# 30x70-motor-controller-0_4.net
KiCad netlist of a schematic drawn in EAGLE
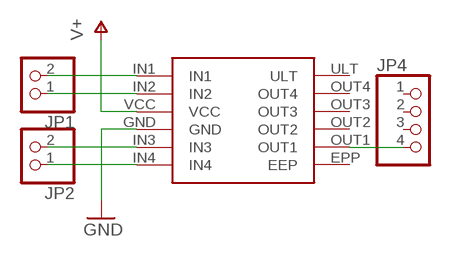
[diagram p0: schematic, sheet 1]
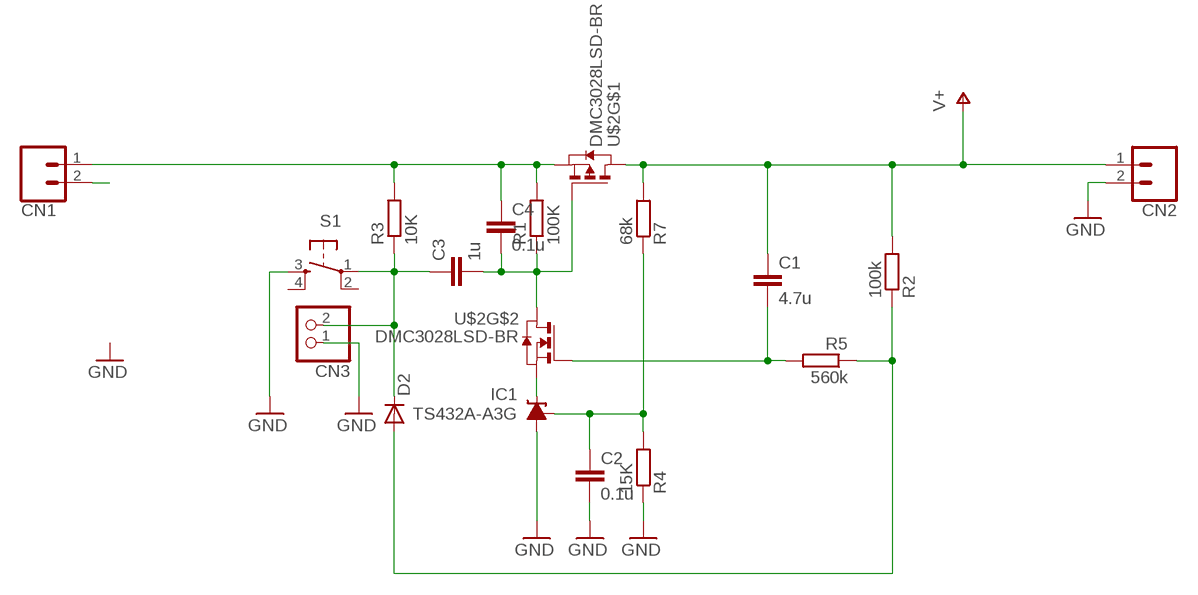
[diagram p1: schematic, sheet 2]

(export (version "E")
  (design (tool "Eeschema 10.0.6"))
  (components
    (comp (ref "C1")
      (value "4.7u")
      (footprint "eagle-import:C025-025X050")
      (libsource (lib "eagle-import") (part "C-EU025-025X050"))
    )
    (comp (ref "C2")
      (value "0.1u")
      (footprint "eagle-import:C025-024X044")
      (libsource (lib "eagle-import") (part "C-EU025-024X044"))
    )
    (comp (ref "C3")
      (value "1u")
      (footprint "eagle-import:C025-024X044")
      (libsource (lib "eagle-import") (part "C-EU025-024X044"))
    )
    (comp (ref "C4")
      (value "0.1u")
      (footprint "eagle-import:C025-024X044")
      (libsource (lib "eagle-import") (part "C-EU025-024X044"))
    )
    (comp (ref "CN1")
      (value "CONN_02-JST-XTH")
      (footprint "eagle-import:JST-2-XTH")
      (libsource (lib "eagle-import") (part "CONN_02-JST-XTH"))
    )
    (comp (ref "CN2")
      (value "CONN_02-JST-XTH")
      (footprint "eagle-import:JST-2-XTH")
      (libsource (lib "eagle-import") (part "CONN_02-JST-XTH"))
    )
    (comp (ref "CN3")
      (value "PINHD-1X2/90")
      (footprint "eagle-import:1X02_90")
      (libsource (lib "eagle-import") (part "PINHD-1X2/90"))
    )
    (comp (ref "D2")
      (value "DIODE-D-2.5")
      (footprint "eagle-import:D-2.5")
      (libsource (lib "eagle-import") (part "DIODE-D-2.5"))
    )
    (comp (ref "IC1")
      (value "TS432A-A3G")
      (footprint "eagle-import:TO92-LINE")
      (libsource (lib "eagle-import") (part "TS432A-A3G"))
    )
    (comp (ref "R1")
      (value "100K")
      (footprint "eagle-import:0204V")
      (libsource (lib "eagle-import") (part "R-EU_0204/2V"))
    )
    (comp (ref "R2")
      (value "100k")
      (footprint "eagle-import:0204V")
      (libsource (lib "eagle-import") (part "R-EU_0204/2V"))
    )
    (comp (ref "R3")
      (value "10K")
      (footprint "eagle-import:0204V")
      (libsource (lib "eagle-import") (part "R-EU_0204/2V"))
    )
    (comp (ref "R4")
      (value "15K")
      (footprint "eagle-import:0204V")
      (libsource (lib "eagle-import") (part "R-EU_0204/2V"))
    )
    (comp (ref "R5")
      (value "560k")
      (footprint "eagle-import:0204_7")
      (libsource (lib "eagle-import") (part "R-EU_0204/7"))
    )
    (comp (ref "R7")
      (value "68k")
      (footprint "eagle-import:0204_7")
      (libsource (lib "eagle-import") (part "R-EU_0204/7"))
    )
    (comp (ref "S1")
      (value "PROTO-MICRO-SWITCH")
      (footprint "eagle-import:B3F-10XX-PROTO")
      (libsource (lib "eagle-import") (part "PROTO-MICRO-SWITCH"))
    )
    (comp (ref "U$2")
      (value "DMC3028LSD-BR")
      (footprint "eagle-import:DIL8-BREAKOUT")
      (libsource (lib "eagle-import") (part "DMC3028LSD-BR"))
    )
    (comp (ref "JP1")
      (value "PINHD-1X2/90")
      (footprint "eagle-import:1X02_90")
      (libsource (lib "eagle-import") (part "PINHD-1X2/90"))
    )
    (comp (ref "JP2")
      (value "PINHD-1X2/90")
      (footprint "eagle-import:1X02_90")
      (libsource (lib "eagle-import") (part "PINHD-1X2/90"))
    )
    (comp (ref "JP4")
      (value "PINHD-1X4/90")
      (footprint "eagle-import:1X04_90")
      (libsource (lib "eagle-import") (part "PINHD-1X4/90"))
    )
    (comp (ref "U$1")
      (value "DRV8833-MODULE")
      (footprint "eagle-import:DRV8833-BRKOUT")
      (libsource (lib "eagle-import") (part "DRV8833-MODULE"))
    )
  )
  (nets
    (net (code "1") (name "GND") (class "Default")
      (node (ref "C2") (pin "2") (pinfunction "2_2") (pintype "passive"))
      (node (ref "CN2") (pin "2") (pinfunction "2_2") (pintype "passive"))
      (node (ref "CN3") (pin "1") (pinfunction "1_1") (pintype "passive"))
      (node (ref "IC1") (pin "2") (pinfunction "A_2") (pintype "passive"))
      (node (ref "R4") (pin "1") (pinfunction "1_1") (pintype "passive"))
      (node (ref "S1") (pin "3") (pinfunction "S_3") (pintype "passive"))
      (node (ref "U$1") (pin "GND") (pinfunction "GND_GND") (pintype "bidirectional"))
    )
    (net (code "2") (name "Net-(D2-PadA)") (class "Default")
      (node (ref "D2") (pin "A") (pinfunction "A_A") (pintype "passive"))
      (node (ref "R2") (pin "1") (pinfunction "1_1") (pintype "passive"))
      (node (ref "R5") (pin "1") (pinfunction "1_1") (pintype "passive"))
    )
    (net (code "3") (name "Net-(IC1-C)") (class "Default")
      (node (ref "IC1") (pin "1") (pinfunction "C_1") (pintype "passive"))
      (node (ref "U$2") (pin "1") (pinfunction "S_1") (pintype "passive"))
    )
    (net (code "4") (name "Net-(IC1-FB)") (class "Default")
      (node (ref "C2") (pin "1") (pinfunction "1_1") (pintype "passive"))
      (node (ref "IC1") (pin "3") (pinfunction "FB_3") (pintype "passive"))
      (node (ref "R4") (pin "2") (pinfunction "2_2") (pintype "passive"))
      (node (ref "R7") (pin "1") (pinfunction "1_1") (pintype "passive"))
    )
    (net (code "5") (name "Net-(JP1-Pad1)") (class "Default")
      (node (ref "JP1") (pin "1") (pinfunction "1_1") (pintype "passive"))
      (node (ref "U$1") (pin "IN2") (pinfunction "IN2_IN2") (pintype "bidirectional"))
    )
    (net (code "6") (name "Net-(JP1-Pad2)") (class "Default")
      (node (ref "JP1") (pin "2") (pinfunction "2_2") (pintype "passive"))
      (node (ref "U$1") (pin "IN1") (pinfunction "IN1_IN1") (pintype "bidirectional"))
    )
    (net (code "7") (name "Net-(JP2-Pad1)") (class "Default")
      (node (ref "JP2") (pin "1") (pinfunction "1_1") (pintype "passive"))
      (node (ref "U$1") (pin "IN4") (pinfunction "IN4_IN4") (pintype "bidirectional"))
    )
    (net (code "8") (name "Net-(JP2-Pad2)") (class "Default")
      (node (ref "JP2") (pin "2") (pinfunction "2_2") (pintype "passive"))
      (node (ref "U$1") (pin "IN3") (pinfunction "IN3_IN3") (pintype "bidirectional"))
    )
    (net (code "9") (name "Net-(JP4-Pad4)") (class "Default")
      (node (ref "JP4") (pin "4") (pinfunction "4_4") (pintype "passive"))
      (node (ref "U$1") (pin "OUT1") (pinfunction "OUT1_OUT1") (pintype "bidirectional"))
    )
    (net (code "10") (name "Net-(S1-P)") (class "Default")
      (node (ref "C3") (pin "1") (pinfunction "1_1") (pintype "passive"))
      (node (ref "CN3") (pin "2") (pinfunction "2_2") (pintype "passive"))
      (node (ref "D2") (pin "C") (pinfunction "C_C") (pintype "passive"))
      (node (ref "R3") (pin "1") (pinfunction "1_1") (pintype "passive"))
      (node (ref "S1") (pin "1") (pinfunction "P_1") (pintype "passive"))
    )
    (net (code "11") (name "Net-(U$2A-G)") (class "Default")
      (node (ref "C3") (pin "2") (pinfunction "2_2") (pintype "passive"))
      (node (ref "C4") (pin "2") (pinfunction "2_2") (pintype "passive"))
      (node (ref "R1") (pin "1") (pinfunction "1_1") (pintype "passive"))
      (node (ref "U$2") (pin "4") (pinfunction "G_4") (pintype "passive"))
      (node (ref "U$2") (pin "7") (pinfunction "D_7") (pintype "passive"))
      (node (ref "U$2") (pin "8") (pinfunction "D_8") (pintype "passive"))
    )
    (net (code "12") (name "Net-(U$2A-S)") (class "Default")
      (node (ref "C4") (pin "1") (pinfunction "1_1") (pintype "passive"))
      (node (ref "CN1") (pin "1") (pinfunction "1_1") (pintype "passive"))
      (node (ref "R1") (pin "2") (pinfunction "2_2") (pintype "passive"))
      (node (ref "R3") (pin "2") (pinfunction "2_2") (pintype "passive"))
      (node (ref "U$2") (pin "3") (pinfunction "S_3") (pintype "passive"))
    )
    (net (code "13") (name "Net-(U$2B-G)") (class "Default")
      (node (ref "C1") (pin "2") (pinfunction "2_2") (pintype "passive"))
      (node (ref "R5") (pin "2") (pinfunction "2_2") (pintype "passive"))
      (node (ref "U$2") (pin "2") (pinfunction "G_2") (pintype "passive"))
    )
    (net (code "14") (name "V+") (class "Default")
      (node (ref "C1") (pin "1") (pinfunction "1_1") (pintype "passive"))
      (node (ref "CN2") (pin "1") (pinfunction "1_1") (pintype "passive"))
      (node (ref "R2") (pin "2") (pinfunction "2_2") (pintype "passive"))
      (node (ref "R7") (pin "2") (pinfunction "2_2") (pintype "passive"))
      (node (ref "U$1") (pin "VCC") (pinfunction "VCC_VCC") (pintype "bidirectional"))
      (node (ref "U$2") (pin "5") (pinfunction "D_5") (pintype "passive"))
      (node (ref "U$2") (pin "6") (pinfunction "D_6") (pintype "passive"))
    )
    (net (code "15") (name "unconnected-(CN1-Pad2)") (class "Default")
      (node (ref "CN1") (pin "2") (pinfunction "2_2") (pintype "passive"))
    )
    (net (code "16") (name "unconnected-(JP4-Pad1)") (class "Default")
      (node (ref "JP4") (pin "1") (pinfunction "1_1") (pintype "passive"))
    )
    (net (code "17") (name "unconnected-(JP4-Pad2)") (class "Default")
      (node (ref "JP4") (pin "2") (pinfunction "2_2") (pintype "passive"))
    )
    (net (code "18") (name "unconnected-(JP4-Pad3)") (class "Default")
      (node (ref "JP4") (pin "3") (pinfunction "3_3") (pintype "passive"))
    )
    (net (code "19") (name "unconnected-(S1-P1-Pad2)") (class "Default")
      (node (ref "S1") (pin "2") (pinfunction "P1_2") (pintype "passive"))
    )
    (net (code "20") (name "unconnected-(S1-S1-Pad4)") (class "Default")
      (node (ref "S1") (pin "4") (pinfunction "S1_4") (pintype "passive"))
    )
    (net (code "21") (name "unconnected-(U$1-EEP-PadEPP)") (class "Default")
      (node (ref "U$1") (pin "EPP") (pinfunction "EEP_EPP") (pintype "bidirectional"))
    )
    (net (code "22") (name "unconnected-(U$1-PadOUT2)") (class "Default")
      (node (ref "U$1") (pin "OUT2") (pinfunction "OUT2_OUT2") (pintype "bidirectional"))
    )
    (net (code "23") (name "unconnected-(U$1-PadOUT3)") (class "Default")
      (node (ref "U$1") (pin "OUT3") (pinfunction "OUT3_OUT3") (pintype "bidirectional"))
    )
    (net (code "24") (name "unconnected-(U$1-PadOUT4)") (class "Default")
      (node (ref "U$1") (pin "OUT4") (pinfunction "OUT4_OUT4") (pintype "bidirectional"))
    )
    (net (code "25") (name "unconnected-(U$1-PadULT)") (class "Default")
      (node (ref "U$1") (pin "ULT") (pinfunction "ULT_ULT") (pintype "bidirectional"))
    )
  )
)
